# Alimenta_o_v3.net
KiCad netlist of a schematic drawn in Altium Designer
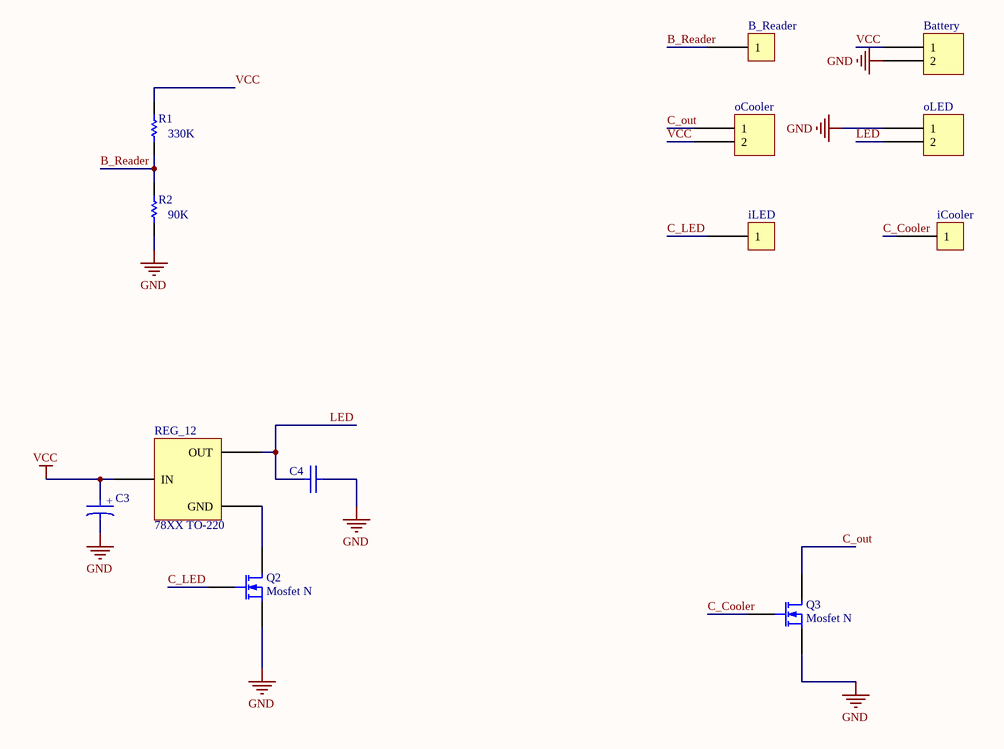
[diagram p0: Alimentação v3.SchDoc]

(export (version "E")
  (design (tool "Eeschema 10.0.6"))
  (components
    (comp (ref "Battery") (value "*") (footprint "XT90") (libsource (lib "Connectors") (part "XT90")))
    (comp (ref "B_Reader")
      (value "*")
      (footprint "HEADER 1X1 8.5MM")
      (libsource (lib "Connectors") (part "Male Pin Head 1x1"))
    )
    (comp (ref "C3")
      (value "*")
      (footprint "Eletrolytic Capacitor 5x5mm")
      (libsource (lib "Components") (part "Electrolytic Capacitor 0.33uF"))
    )
    (comp (ref "C4")
      (value "*")
      (footprint "SMD Capacitor")
      (libsource (lib "Components") (part "Capacitor SMD 0805"))
    )
    (comp (ref "iCooler")
      (value "*")
      (footprint "HEADER 1X1 8.5MM")
      (libsource (lib "Connectors") (part "Male Pin Head 1x1"))
    )
    (comp (ref "iLED")
      (value "*")
      (footprint "HEADER 1X1 8.5MM")
      (libsource (lib "Connectors") (part "Male Pin Head 1x1"))
    )
    (comp (ref "oCooler")
      (value "*")
      (footprint "KK2")
      (description "KK Connector, 2 ways")
      (libsource (lib "Connectors") (part "KK2"))
    )
    (comp (ref "oLED")
      (value "*")
      (footprint "KK2")
      (description "KK Connector, 2 ways")
      (libsource (lib "Connectors") (part "KK2"))
    )
    (comp (ref "Q2") (value "Mosfet N") (footprint "TO-220") (libsource (lib "Components") (part "Mosfet N")))
    (comp (ref "Q3") (value "Mosfet N") (footprint "TO-220") (libsource (lib "Components") (part "Mosfet N")))
    (comp (ref "R1")
      (value "330K")
      (footprint "RESISTOR THT 5mm")
      (fields (field (name "Comment") "Resistor THT"))
      (libsource (lib "Components") (part "Resistor THT"))
    )
    (comp (ref "R2")
      (value "90K")
      (footprint "RESISTOR THT 5mm")
      (fields (field (name "Comment") "Resistor THT"))
      (libsource (lib "Components") (part "Resistor THT"))
    )
    (comp (ref "REG_12")
      (value "78XX TO-220")
      (footprint "TO-220")
      (libsource (lib "Components") (part "78XX TO-220"))
    )
  )
  (nets
    (net (code "1") (name "/B_Reader") (class "Default")
      (node (ref "B_Reader") (pin "1") (pinfunction "1_1") (pintype "passive"))
      (node (ref "R1") (pin "1") (pinfunction "1_1") (pintype "passive"))
      (node (ref "R2") (pin "2") (pinfunction "2_2") (pintype "passive"))
    )
    (net (code "2") (name "/C_Cooler") (class "Default")
      (node (ref "Q3") (pin "2") (pinfunction "G_2") (pintype "passive"))
      (node (ref "iCooler") (pin "1") (pinfunction "1_1") (pintype "passive"))
    )
    (net (code "3") (name "/C_LED") (class "Default")
      (node (ref "Q2") (pin "2") (pinfunction "G_2") (pintype "passive"))
      (node (ref "iLED") (pin "1") (pinfunction "1_1") (pintype "passive"))
    )
    (net (code "4") (name "/C_out") (class "Default")
      (node (ref "Q3") (pin "3") (pinfunction "D_3") (pintype "passive"))
      (node (ref "oCooler") (pin "1") (pinfunction "1_1") (pintype "passive"))
    )
    (net (code "5") (name "/LED") (class "Default")
      (node (ref "C4") (pin "2") (pintype "passive"))
      (node (ref "REG_12") (pin "3") (pinfunction "OUT_3") (pintype "passive"))
      (node (ref "oLED") (pin "2") (pinfunction "2_2") (pintype "passive"))
    )
    (net (code "6") (name "GND") (class "Default")
      (node (ref "Battery") (pin "2") (pinfunction "2_2") (pintype "passive"))
      (node (ref "C3") (pin "2") (pintype "passive"))
      (node (ref "C4") (pin "1") (pintype "passive"))
      (node (ref "Q2") (pin "1") (pinfunction "S_1") (pintype "passive"))
      (node (ref "Q3") (pin "1") (pinfunction "S_1") (pintype "passive"))
      (node (ref "R2") (pin "1") (pinfunction "1_1") (pintype "passive"))
      (node (ref "oLED") (pin "1") (pinfunction "1_1") (pintype "passive"))
    )
    (net (code "7") (name "Net-(Q2-D)") (class "Default")
      (node (ref "Q2") (pin "3") (pinfunction "D_3") (pintype "passive"))
      (node (ref "REG_12") (pin "2") (pinfunction "GND_2") (pintype "passive"))
    )
    (net (code "8") (name "VCC") (class "Default")
      (node (ref "Battery") (pin "1") (pinfunction "1_1") (pintype "passive"))
      (node (ref "C3") (pin "1") (pintype "passive"))
      (node (ref "R1") (pin "2") (pinfunction "2_2") (pintype "passive"))
      (node (ref "REG_12") (pin "1") (pinfunction "IN_1") (pintype "passive"))
      (node (ref "oCooler") (pin "2") (pinfunction "2_2") (pintype "passive"))
    )
  )
)
